# 2020.net
KiCad netlist of a schematic drawn in Altium Designer
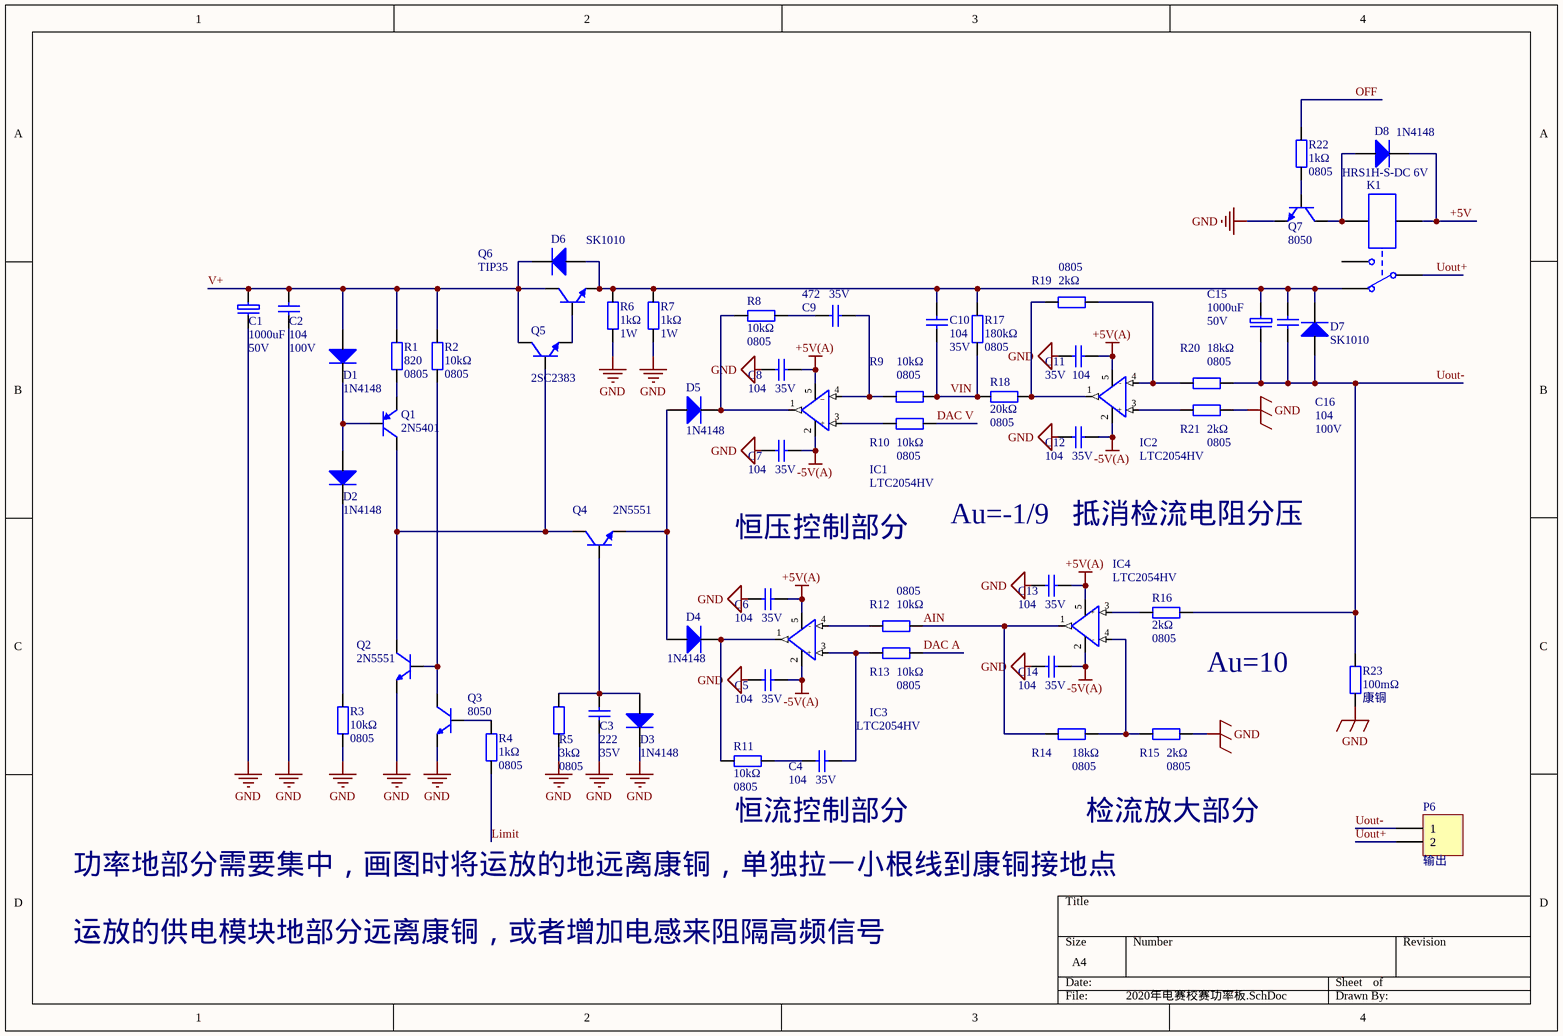
[diagram p0: 2020年电赛校赛功率板.SchDoc]

(export (version "E")
  (design (tool "Eeschema 10.0.6"))
  (components
    (comp (ref "C1")
      (value "1000uF")
      (footprint "CR132(Φ13.2,间距5.1)")
      (description "有极性电容")
      (fields (field (name "ALTIUM_VALUE") "50V"))
      (libsource (lib "原理图库") (part "100uF"))
    )
    (comp (ref "C2")
      (value "104")
      (footprint "C0805")
      (description "无极性电容")
      (fields (field (name "ALTIUM_VALUE") "100V"))
      (libsource (lib "原理图库") (part "104"))
    )
    (comp (ref "C3")
      (value "222")
      (footprint "C0805")
      (description "无极性电容")
      (fields (field (name "ALTIUM_VALUE") "35V"))
      (libsource (lib "原理图库") (part "104"))
    )
    (comp (ref "C4")
      (value "104")
      (footprint "C0805")
      (description "无极性电容")
      (fields (field (name "ALTIUM_VALUE") "35V"))
      (libsource (lib "原理图库") (part "104"))
    )
    (comp (ref "C5")
      (value "104")
      (footprint "C0805")
      (description "无极性电容")
      (fields (field (name "ALTIUM_VALUE") "35V"))
      (libsource (lib "原理图库") (part "104"))
    )
    (comp (ref "C6")
      (value "104")
      (footprint "C0805")
      (description "无极性电容")
      (fields (field (name "ALTIUM_VALUE") "35V"))
      (libsource (lib "原理图库") (part "104"))
    )
    (comp (ref "C7")
      (value "104")
      (footprint "C0805")
      (description "无极性电容")
      (fields (field (name "ALTIUM_VALUE") "35V"))
      (libsource (lib "原理图库") (part "104"))
    )
    (comp (ref "C8")
      (value "104")
      (footprint "C0805")
      (description "无极性电容")
      (fields (field (name "ALTIUM_VALUE") "35V"))
      (libsource (lib "原理图库") (part "104"))
    )
    (comp (ref "C9")
      (value "472")
      (footprint "C0805")
      (description "无极性电容")
      (fields (field (name "ALTIUM_VALUE") "35V"))
      (libsource (lib "原理图库") (part "104"))
    )
    (comp (ref "C10")
      (value "104")
      (footprint "C0805")
      (description "无极性电容")
      (fields (field (name "ALTIUM_VALUE") "35V"))
      (libsource (lib "原理图库") (part "104"))
    )
    (comp (ref "C11")
      (value "104")
      (footprint "C0805")
      (description "无极性电容")
      (fields (field (name "ALTIUM_VALUE") "35V"))
      (libsource (lib "原理图库") (part "104"))
    )
    (comp (ref "C12")
      (value "104")
      (footprint "C0805")
      (description "无极性电容")
      (fields (field (name "ALTIUM_VALUE") "35V"))
      (libsource (lib "原理图库") (part "104"))
    )
    (comp (ref "C13")
      (value "104")
      (footprint "C0805")
      (description "无极性电容")
      (fields (field (name "ALTIUM_VALUE") "35V"))
      (libsource (lib "原理图库") (part "104"))
    )
    (comp (ref "C14")
      (value "104")
      (footprint "C0805")
      (description "无极性电容")
      (fields (field (name "ALTIUM_VALUE") "35V"))
      (libsource (lib "原理图库") (part "104"))
    )
    (comp (ref "C15")
      (value "1000uF")
      (footprint "CR132(Φ13.2,间距5.1)")
      (description "有极性电容")
      (fields (field (name "ALTIUM_VALUE") "50V"))
      (libsource (lib "原理图库") (part "100uF"))
    )
    (comp (ref "C16")
      (value "104")
      (footprint "C0805")
      (description "无极性电容")
      (fields (field (name "ALTIUM_VALUE") "100V"))
      (libsource (lib "原理图库") (part "104"))
    )
    (comp (ref "D1")
      (value "1N4148")
      (footprint "LL34")
      (description "二极管")
      (libsource (lib "原理图库") (part "Diode"))
    )
    (comp (ref "D2")
      (value "1N4148")
      (footprint "LL34")
      (description "二极管")
      (libsource (lib "原理图库") (part "Diode"))
    )
    (comp (ref "D3")
      (value "1N4148")
      (footprint "LL34")
      (description "二极管")
      (libsource (lib "原理图库") (part "Diode"))
    )
    (comp (ref "D4")
      (value "1N4148")
      (footprint "LL34")
      (description "二极管")
      (libsource (lib "原理图库") (part "Diode"))
    )
    (comp (ref "D5")
      (value "1N4148")
      (footprint "LL34")
      (description "二极管")
      (libsource (lib "原理图库") (part "Diode"))
    )
    (comp (ref "D6")
      (value "SK1010")
      (footprint "SMC(DO-214AB)")
      (description "二极管")
      (libsource (lib "原理图库") (part "Diode"))
    )
    (comp (ref "D7")
      (value "SK1010")
      (footprint "SMC(DO-214AB)")
      (description "二极管")
      (libsource (lib "原理图库") (part "Diode"))
    )
    (comp (ref "D8")
      (value "1N4148")
      (footprint "LL34")
      (description "二极管")
      (libsource (lib "原理图库") (part "Diode"))
    )
    (comp (ref "IC1")
      (value "LTC2054HV")
      (footprint "TSOT-32-5")
      (description "运放")
      (libsource (lib "") (part "OPA350UA_1"))
    )
    (comp (ref "IC2")
      (value "LTC2054HV")
      (footprint "TSOT-32-5")
      (description "运放")
      (libsource (lib "") (part "OPA350UA_1"))
    )
    (comp (ref "IC3")
      (value "LTC2054HV")
      (footprint "TSOT-32-5")
      (description "运放")
      (libsource (lib "") (part "OPA350UA_1"))
    )
    (comp (ref "IC4")
      (value "LTC2054HV")
      (footprint "TSOT-32-5")
      (description "运放")
      (libsource (lib "原理图库") (part "OPA350UA"))
    )
    (comp (ref "K1")
      (value "HRS1H-S-DC 6V")
      (footprint "继电器")
      (description "继电器")
      (libsource (lib "原理图库") (part "HRS1H-S-DC 6V"))
    )
    (comp (ref "P6")
      (value "输出")
      (footprint "KF7.62-2P")
      (description "Header, 2-Pin")
      (fields (field (name "PUBLISHER") "Altium Limited"))
      (libsource (lib "Miscellaneous Connectors") (part "Header 2"))
    )
    (comp (ref "Q1") (value "2N5401") (footprint "SOT-23") (libsource (lib "原理图库") (part "PNP")))
    (comp (ref "Q2") (value "2N5551") (footprint "SOT-23") (libsource (lib "原理图库") (part "NPN!")))
    (comp (ref "Q3")
      (value "8050")
      (footprint "SOT-23")
      (description "三极管")
      (libsource (lib "原理图库") (part "NPN!"))
    )
    (comp (ref "Q4")
      (value "2N5551")
      (footprint "SOT-23")
      (description "三极管")
      (libsource (lib "原理图库") (part "NPN"))
    )
    (comp (ref "Q5")
      (value "2SC2383")
      (footprint "TO-92")
      (description "三极管")
      (libsource (lib "") (part "NPN_1"))
    )
    (comp (ref "Q6")
      (value "TIP35")
      (footprint "TO-247")
      (description "三极管")
      (libsource (lib "原理图库") (part "NPN"))
    )
    (comp (ref "Q7")
      (value "8050")
      (footprint "SOT-23")
      (description "三极管")
      (libsource (lib "") (part "NPN_2"))
    )
    (comp (ref "R1")
      (value "820")
      (footprint "R0805")
      (description "贴片/直插电阻")
      (fields (field (name "ALTIUM_VALUE") "0805"))
      (libsource (lib "原理图库") (part "10kΩ"))
    )
    (comp (ref "R2")
      (value "10kΩ")
      (footprint "R0805")
      (description "贴片/直插电阻")
      (fields (field (name "ALTIUM_VALUE") "0805"))
      (libsource (lib "原理图库") (part "10kΩ"))
    )
    (comp (ref "R3")
      (value "10kΩ")
      (footprint "R0805")
      (description "贴片/直插电阻")
      (fields (field (name "ALTIUM_VALUE") "0805"))
      (libsource (lib "原理图库") (part "10kΩ"))
    )
    (comp (ref "R4")
      (value "1kΩ")
      (footprint "R0805")
      (description "贴片/直插电阻")
      (fields (field (name "ALTIUM_VALUE") "0805"))
      (libsource (lib "原理图库") (part "10kΩ"))
    )
    (comp (ref "R5")
      (value "3kΩ")
      (footprint "R0805")
      (description "贴片/直插电阻")
      (fields (field (name "ALTIUM_VALUE") "0805"))
      (libsource (lib "原理图库") (part "10kΩ"))
    )
    (comp (ref "R6")
      (value "1kΩ")
      (footprint "RES-1W(立式)")
      (description "贴片/直插电阻")
      (fields (field (name "ALTIUM_VALUE") "1W"))
      (libsource (lib "原理图库") (part "10kΩ"))
    )
    (comp (ref "R7")
      (value "1kΩ")
      (footprint "RES-1W(立式)")
      (description "贴片/直插电阻")
      (fields (field (name "ALTIUM_VALUE") "1W"))
      (libsource (lib "原理图库") (part "10kΩ"))
    )
    (comp (ref "R8")
      (value "10kΩ")
      (footprint "R0805")
      (description "贴片/直插电阻")
      (fields (field (name "ALTIUM_VALUE") "0805"))
      (libsource (lib "原理图库") (part "10kΩ"))
    )
    (comp (ref "R9")
      (value "10kΩ")
      (footprint "R0805")
      (description "贴片/直插电阻")
      (fields (field (name "ALTIUM_VALUE") "0805"))
      (libsource (lib "原理图库") (part "10kΩ"))
    )
    (comp (ref "R10")
      (value "10kΩ")
      (footprint "R0805")
      (description "贴片/直插电阻")
      (fields (field (name "ALTIUM_VALUE") "0805"))
      (libsource (lib "原理图库") (part "10kΩ"))
    )
    (comp (ref "R11")
      (value "10kΩ")
      (footprint "R0805")
      (description "贴片/直插电阻")
      (fields (field (name "ALTIUM_VALUE") "0805"))
      (libsource (lib "原理图库") (part "10kΩ"))
    )
    (comp (ref "R12")
      (value "10kΩ")
      (footprint "R0805")
      (description "贴片/直插电阻")
      (fields (field (name "ALTIUM_VALUE") "0805"))
      (libsource (lib "原理图库") (part "10kΩ"))
    )
    (comp (ref "R13")
      (value "10kΩ")
      (footprint "R0805")
      (description "贴片/直插电阻")
      (fields (field (name "ALTIUM_VALUE") "0805"))
      (libsource (lib "原理图库") (part "10kΩ"))
    )
    (comp (ref "R14")
      (value "18kΩ")
      (footprint "R0805")
      (description "贴片/直插电阻")
      (fields (field (name "ALTIUM_VALUE") "0805"))
      (libsource (lib "原理图库") (part "10kΩ"))
    )
    (comp (ref "R15")
      (value "2kΩ")
      (footprint "R0805")
      (description "贴片/直插电阻")
      (fields (field (name "ALTIUM_VALUE") "0805"))
      (libsource (lib "原理图库") (part "10kΩ"))
    )
    (comp (ref "R16")
      (value "2kΩ")
      (footprint "R0805")
      (description "贴片/直插电阻")
      (fields (field (name "ALTIUM_VALUE") "0805"))
      (libsource (lib "原理图库") (part "10kΩ"))
    )
    (comp (ref "R17")
      (value "180kΩ")
      (footprint "R0805")
      (description "贴片/直插电阻")
      (fields (field (name "ALTIUM_VALUE") "0805"))
      (libsource (lib "原理图库") (part "10kΩ"))
    )
    (comp (ref "R18")
      (value "20kΩ")
      (footprint "R0805")
      (description "贴片/直插电阻")
      (fields (field (name "ALTIUM_VALUE") "0805"))
      (libsource (lib "原理图库") (part "10kΩ"))
    )
    (comp (ref "R19")
      (value "2kΩ")
      (footprint "R0805")
      (description "贴片/直插电阻")
      (fields (field (name "ALTIUM_VALUE") "0805"))
      (libsource (lib "原理图库") (part "10kΩ"))
    )
    (comp (ref "R20")
      (value "18kΩ")
      (footprint "R0805")
      (description "贴片/直插电阻")
      (fields (field (name "ALTIUM_VALUE") "0805"))
      (libsource (lib "原理图库") (part "10kΩ"))
    )
    (comp (ref "R21")
      (value "2kΩ")
      (footprint "R0805")
      (description "贴片/直插电阻")
      (fields (field (name "ALTIUM_VALUE") "0805"))
      (libsource (lib "原理图库") (part "10kΩ"))
    )
    (comp (ref "R22")
      (value "1kΩ")
      (footprint "R0805")
      (description "贴片/直插电阻")
      (fields (field (name "ALTIUM_VALUE") "0805"))
      (libsource (lib "原理图库") (part "10kΩ"))
    )
    (comp (ref "R23")
      (value "100mΩ")
      (footprint "100mΩ康铜")
      (description "贴片/直插电阻")
      (fields (field (name "ALTIUM_VALUE") "康铜"))
      (libsource (lib "原理图库") (part "10kΩ"))
    )
  )
  (nets
    (net (code "1") (name "+5V(A)") (class "Default")
      (node (ref "C11") (pin "2") (pintype "passive"))
      (node (ref "C13") (pin "2") (pintype "passive"))
      (node (ref "C6") (pin "2") (pintype "passive"))
      (node (ref "C8") (pin "2") (pintype "passive"))
      (node (ref "IC1") (pin "5") (pintype "passive"))
      (node (ref "IC2") (pin "5") (pintype "passive"))
      (node (ref "IC3") (pin "5") (pintype "passive"))
      (node (ref "IC4") (pin "5") (pintype "passive"))
    )
    (net (code "2") (name "-5V(A)") (class "Default")
      (node (ref "C12") (pin "2") (pintype "passive"))
      (node (ref "C14") (pin "2") (pintype "passive"))
      (node (ref "C5") (pin "2") (pintype "passive"))
      (node (ref "C7") (pin "2") (pintype "passive"))
      (node (ref "IC1") (pin "2") (pintype "passive"))
      (node (ref "IC2") (pin "2") (pintype "passive"))
      (node (ref "IC3") (pin "2") (pintype "passive"))
      (node (ref "IC4") (pin "2") (pintype "passive"))
    )
    (net (code "3") (name "/+5V") (class "Default")
      (node (ref "D8") (pin "2") (pinfunction "K_2") (pintype "passive"))
      (node (ref "K1") (pin "2") (pinfunction "2_2") (pintype "passive"))
    )
    (net (code "4") (name "/AIN") (class "Default")
      (node (ref "IC4") (pin "1") (pintype "output"))
      (node (ref "R12") (pin "2") (pintype "passive"))
      (node (ref "R14") (pin "2") (pintype "passive"))
    )
    (net (code "5") (name "/DAC A") (class "Default") (node (ref "R13") (pin "2") (pintype "passive")))
    (net (code "6") (name "/DAC V") (class "Default") (node (ref "R10") (pin "2") (pintype "passive")))
    (net (code "7") (name "/Limit") (class "Default") (node (ref "R4") (pin "1") (pintype "passive")))
    (net (code "8") (name "/OFF") (class "Default") (node (ref "R22") (pin "2") (pintype "passive")))
    (net (code "9") (name "/Uout+") (class "Default")
      (node (ref "K1") (pin "4") (pinfunction "4_4") (pintype "passive"))
      (node (ref "P6") (pin "2") (pinfunction "2_2") (pintype "passive"))
    )
    (net (code "10") (name "/Uout-") (class "Default")
      (node (ref "C15") (pin "2") (pinfunction "-_2") (pintype "passive"))
      (node (ref "C16") (pin "1") (pintype "passive"))
      (node (ref "D7") (pin "1") (pinfunction "A_1") (pintype "passive"))
      (node (ref "P6") (pin "1") (pinfunction "1_1") (pintype "passive"))
      (node (ref "R16") (pin "1") (pintype "passive"))
      (node (ref "R20") (pin "1") (pintype "passive"))
      (node (ref "R23") (pin "1") (pintype "passive"))
    )
    (net (code "11") (name "/V+") (class "Default")
      (node (ref "C1") (pin "1") (pinfunction "+_1") (pintype "passive"))
      (node (ref "C2") (pin "2") (pintype "passive"))
      (node (ref "D1") (pin "1") (pinfunction "A_1") (pintype "passive"))
      (node (ref "D6") (pin "2") (pinfunction "K_2") (pintype "passive"))
      (node (ref "Q5") (pin "2") (pinfunction "C_2") (pintype "passive"))
      (node (ref "Q6") (pin "2") (pinfunction "C_2") (pintype "passive"))
      (node (ref "R1") (pin "2") (pintype "passive"))
      (node (ref "R2") (pin "2") (pintype "passive"))
    )
    (net (code "12") (name "/VIN") (class "Default")
      (node (ref "C10") (pin "1") (pintype "passive"))
      (node (ref "R17") (pin "1") (pintype "passive"))
      (node (ref "R18") (pin "1") (pintype "passive"))
      (node (ref "R9") (pin "2") (pintype "passive"))
    )
    (net (code "13") (name "GND") (class "Default")
      (node (ref "C1") (pin "2") (pinfunction "-_2") (pintype "passive"))
      (node (ref "C11") (pin "1") (pintype "passive"))
      (node (ref "C12") (pin "1") (pintype "passive"))
      (node (ref "C13") (pin "1") (pintype "passive"))
      (node (ref "C14") (pin "1") (pintype "passive"))
      (node (ref "C2") (pin "1") (pintype "passive"))
      (node (ref "C3") (pin "1") (pintype "passive"))
      (node (ref "C5") (pin "1") (pintype "passive"))
      (node (ref "C6") (pin "1") (pintype "passive"))
      (node (ref "C7") (pin "1") (pintype "passive"))
      (node (ref "C8") (pin "1") (pintype "passive"))
      (node (ref "D3") (pin "2") (pinfunction "K_2") (pintype "passive"))
      (node (ref "Q2") (pin "3") (pinfunction "E_3") (pintype "passive"))
      (node (ref "Q3") (pin "3") (pinfunction "E_3") (pintype "passive"))
      (node (ref "Q7") (pin "3") (pinfunction "E_3") (pintype "passive"))
      (node (ref "R15") (pin "1") (pintype "passive"))
      (node (ref "R21") (pin "1") (pintype "passive"))
      (node (ref "R23") (pin "2") (pintype "passive"))
      (node (ref "R3") (pin "1") (pintype "passive"))
      (node (ref "R5") (pin "1") (pintype "passive"))
      (node (ref "R6") (pin "1") (pintype "passive"))
      (node (ref "R7") (pin "1") (pintype "passive"))
    )
    (net (code "14") (name "Net-(C4-Pad1)") (class "Default")
      (node (ref "C4") (pin "1") (pintype "passive"))
      (node (ref "R11") (pin "2") (pintype "passive"))
    )
    (net (code "15") (name "Net-(C9-Pad1)") (class "Default")
      (node (ref "C9") (pin "1") (pintype "passive"))
      (node (ref "R8") (pin "2") (pintype "passive"))
    )
    (net (code "16") (name "Net-(C15-+)") (class "Default")
      (node (ref "C10") (pin "2") (pintype "passive"))
      (node (ref "C15") (pin "1") (pinfunction "+_1") (pintype "passive"))
      (node (ref "C16") (pin "2") (pintype "passive"))
      (node (ref "D6") (pin "1") (pinfunction "A_1") (pintype "passive"))
      (node (ref "D7") (pin "2") (pinfunction "K_2") (pintype "passive"))
      (node (ref "K1") (pin "1") (pinfunction "1_1") (pintype "passive"))
      (node (ref "Q6") (pin "3") (pinfunction "E_3") (pintype "passive"))
      (node (ref "R17") (pin "2") (pintype "passive"))
      (node (ref "R6") (pin "2") (pintype "passive"))
      (node (ref "R7") (pin "2") (pintype "passive"))
    )
    (net (code "17") (name "Net-(D1-K)") (class "Default")
      (node (ref "D1") (pin "2") (pinfunction "K_2") (pintype "passive"))
      (node (ref "D2") (pin "1") (pinfunction "A_1") (pintype "passive"))
      (node (ref "Q1") (pin "1") (pinfunction "B_1") (pintype "passive"))
    )
    (net (code "18") (name "Net-(D2-K)") (class "Default")
      (node (ref "D2") (pin "2") (pinfunction "K_2") (pintype "passive"))
      (node (ref "R3") (pin "2") (pintype "passive"))
    )
    (net (code "19") (name "Net-(D3-A)") (class "Default")
      (node (ref "C3") (pin "2") (pintype "passive"))
      (node (ref "D3") (pin "1") (pinfunction "A_1") (pintype "passive"))
      (node (ref "Q4") (pin "1") (pinfunction "B_1") (pintype "passive"))
      (node (ref "R5") (pin "2") (pintype "passive"))
    )
    (net (code "20") (name "Net-(D4-A)") (class "Default")
      (node (ref "D4") (pin "1") (pinfunction "A_1") (pintype "passive"))
      (node (ref "D5") (pin "1") (pinfunction "A_1") (pintype "passive"))
      (node (ref "Q4") (pin "3") (pinfunction "E_3") (pintype "passive"))
    )
    (net (code "21") (name "Net-(D4-K)") (class "Default")
      (node (ref "D4") (pin "2") (pinfunction "K_2") (pintype "passive"))
      (node (ref "IC3") (pin "1") (pintype "output"))
      (node (ref "R11") (pin "1") (pintype "passive"))
    )
    (net (code "22") (name "Net-(D5-K)") (class "Default")
      (node (ref "D5") (pin "2") (pinfunction "K_2") (pintype "passive"))
      (node (ref "IC1") (pin "1") (pintype "output"))
      (node (ref "R8") (pin "1") (pintype "passive"))
    )
    (net (code "23") (name "Net-(D8-A)") (class "Default")
      (node (ref "D8") (pin "1") (pinfunction "A_1") (pintype "passive"))
      (node (ref "K1") (pin "5") (pinfunction "5_5") (pintype "passive"))
      (node (ref "Q7") (pin "1") (pinfunction "C_1") (pintype "passive"))
    )
    (net (code "24") (name "Net-(IC1-+)") (class "Default")
      (node (ref "IC1") (pin "3") (pinfunction "+_3") (pintype "input"))
      (node (ref "R10") (pin "1") (pintype "passive"))
    )
    (net (code "25") (name "Net-(IC1--)") (class "Default")
      (node (ref "C9") (pin "2") (pintype "passive"))
      (node (ref "IC1") (pin "4") (pinfunction "-_4") (pintype "input"))
      (node (ref "R9") (pin "1") (pintype "passive"))
    )
    (net (code "26") (name "Net-(IC2-+)") (class "Default")
      (node (ref "IC2") (pin "3") (pinfunction "+_3") (pintype "input"))
      (node (ref "R21") (pin "2") (pintype "passive"))
    )
    (net (code "27") (name "Net-(IC2--)") (class "Default")
      (node (ref "IC2") (pin "4") (pinfunction "-_4") (pintype "input"))
      (node (ref "R19") (pin "1") (pintype "passive"))
      (node (ref "R20") (pin "2") (pintype "passive"))
    )
    (net (code "28") (name "Net-(IC2-Pad1)") (class "Default")
      (node (ref "IC2") (pin "1") (pintype "output"))
      (node (ref "R18") (pin "2") (pintype "passive"))
      (node (ref "R19") (pin "2") (pintype "passive"))
    )
    (net (code "29") (name "Net-(IC3-+)") (class "Default")
      (node (ref "C4") (pin "2") (pintype "passive"))
      (node (ref "IC3") (pin "3") (pinfunction "+_3") (pintype "input"))
      (node (ref "R13") (pin "1") (pintype "passive"))
    )
    (net (code "30") (name "Net-(IC3--)") (class "Default")
      (node (ref "IC3") (pin "4") (pinfunction "-_4") (pintype "input"))
      (node (ref "R12") (pin "1") (pintype "passive"))
    )
    (net (code "31") (name "Net-(IC4-+)") (class "Default")
      (node (ref "IC4") (pin "3") (pinfunction "+_3") (pintype "input"))
      (node (ref "R16") (pin "2") (pintype "passive"))
    )
    (net (code "32") (name "Net-(IC4--)") (class "Default")
      (node (ref "IC4") (pin "4") (pinfunction "-_4") (pintype "input"))
      (node (ref "R14") (pin "1") (pintype "passive"))
      (node (ref "R15") (pin "2") (pintype "passive"))
    )
    (net (code "33") (name "Net-(Q1-C)") (class "Default")
      (node (ref "Q1") (pin "2") (pinfunction "C_2") (pintype "passive"))
      (node (ref "Q2") (pin "2") (pinfunction "C_2") (pintype "passive"))
      (node (ref "Q4") (pin "2") (pinfunction "C_2") (pintype "passive"))
      (node (ref "Q5") (pin "3") (pinfunction "B_3") (pintype "passive"))
    )
    (net (code "34") (name "Net-(Q1-E)") (class "Default")
      (node (ref "Q1") (pin "3") (pinfunction "E_3") (pintype "passive"))
      (node (ref "R1") (pin "1") (pintype "passive"))
    )
    (net (code "35") (name "Net-(Q2-B)") (class "Default")
      (node (ref "Q2") (pin "1") (pinfunction "B_1") (pintype "passive"))
      (node (ref "Q3") (pin "2") (pinfunction "C_2") (pintype "passive"))
      (node (ref "R2") (pin "1") (pintype "passive"))
    )
    (net (code "36") (name "Net-(Q3-B)") (class "Default")
      (node (ref "Q3") (pin "1") (pinfunction "B_1") (pintype "passive"))
      (node (ref "R4") (pin "2") (pintype "passive"))
    )
    (net (code "37") (name "Net-(Q5-E)") (class "Default")
      (node (ref "Q5") (pin "1") (pinfunction "E_1") (pintype "passive"))
      (node (ref "Q6") (pin "1") (pinfunction "B_1") (pintype "passive"))
    )
    (net (code "38") (name "Net-(Q7-B)") (class "Default")
      (node (ref "Q7") (pin "2") (pinfunction "B_2") (pintype "passive"))
      (node (ref "R22") (pin "1") (pintype "passive"))
    )
    (net (code "39") (name "unconnected-(K1-Pad6)") (class "Default")
      (node (ref "K1") (pin "6") (pinfunction "6_6") (pintype "passive"))
    )
  )
)
